# Sheet1.net
KiCad netlist of a schematic drawn in Altium Designer
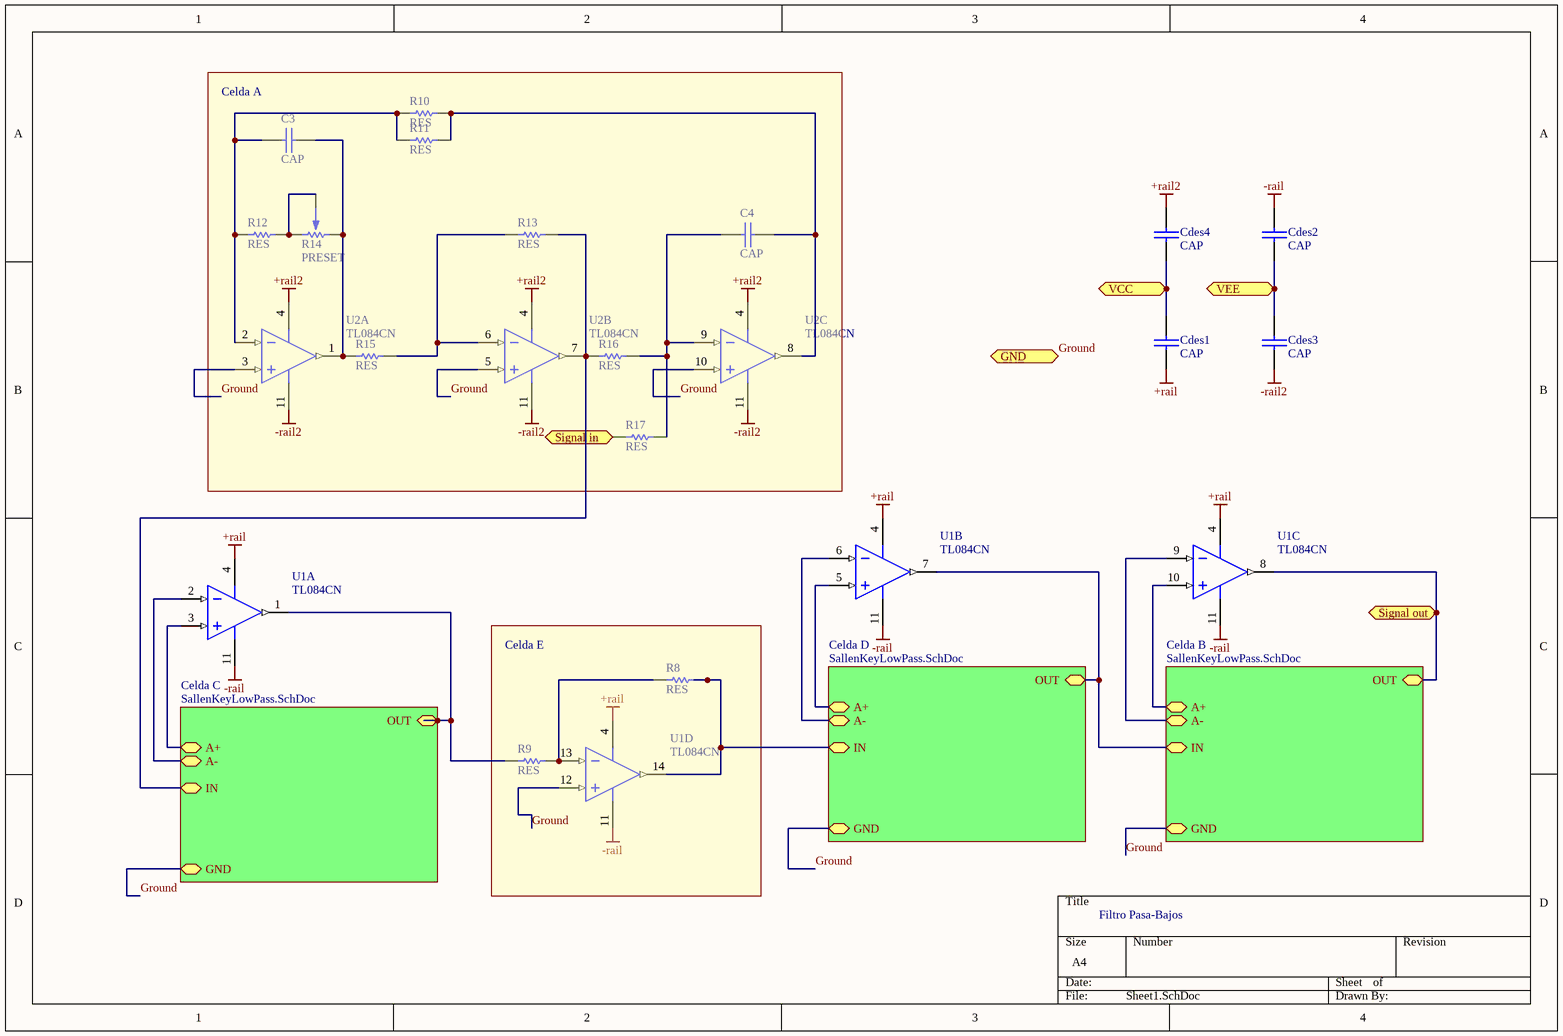
[diagram p0: Sheet1.SchDoc]

(export (version "E")
  (design (tool "Eeschema 10.0.6"))
  (components
    (comp (ref "C3") (value "CAP") (footprint "CAP100") (libsource (lib "LIBEBAL") (part "CAP")))
    (comp (ref "C4") (value "CAP") (footprint "CAP100") (libsource (lib "LIBEBAL") (part "CAP")))
    (comp (ref "Cdes1") (value "CAP") (footprint "CAP100") (libsource (lib "LIBEBAL") (part "CAP")))
    (comp (ref "Cdes2") (value "CAP") (footprint "CAP100") (libsource (lib "LIBEBAL") (part "CAP")))
    (comp (ref "Cdes3") (value "CAP") (footprint "CAP100") (libsource (lib "LIBEBAL") (part "CAP")))
    (comp (ref "Cdes4") (value "CAP") (footprint "CAP100") (libsource (lib "LIBEBAL") (part "CAP")))
    (comp (ref "R8") (value "RES") (footprint "RES300") (libsource (lib "LIBEBAL") (part "RES")))
    (comp (ref "R9") (value "RES") (footprint "RES300") (libsource (lib "LIBEBAL") (part "RES")))
    (comp (ref "R10") (value "RES") (footprint "RES300") (libsource (lib "LIBEBAL") (part "RES")))
    (comp (ref "R11") (value "RES") (footprint "RES300") (libsource (lib "LIBEBAL") (part "RES")))
    (comp (ref "R12") (value "RES") (footprint "RES300") (libsource (lib "LIBEBAL") (part "RES")))
    (comp (ref "R13") (value "RES") (footprint "RES300") (libsource (lib "LIBEBAL") (part "RES")))
    (comp (ref "R14") (value "PRESET") (footprint "PRESET V") (libsource (lib "LIBEBAL") (part "PRESET")))
    (comp (ref "R15") (value "RES") (footprint "RES300") (libsource (lib "LIBEBAL") (part "RES")))
    (comp (ref "R16") (value "RES") (footprint "RES300") (libsource (lib "LIBEBAL") (part "RES")))
    (comp (ref "R17") (value "RES") (footprint "RES300") (libsource (lib "LIBEBAL") (part "RES")))
    (comp (ref "U1")
      (value "TL084CN")
      (footprint "TI-N14")
      (description "JFET-Input Operational Amplifier, 7 to 36 V, 0 to 70 degC, 14-pin DIP (N14), Pb-Free (RoHS)")
      (fields (field (name "MANUFACTURER") "Texas Instruments"))
      (libsource (lib "TI Amplifiers and Linear Operational Amplifier General Purpose") (part "TL084CN"))
    )
    (comp (ref "U2")
      (value "TL084CN")
      (footprint "TI-N14")
      (description "JFET-Input Operational Amplifier, 7 to 36 V, 0 to 70 degC, 14-pin DIP (N14), Pb-Free (RoHS)")
      (fields (field (name "MANUFACTURER") "Texas Instruments"))
      (libsource (lib "TI Amplifiers and Linear Operational Amplifier General Purpose") (part "TL084CN"))
    )
  )
  (nets
    (net (code "1") (name "+rail") (class "Default")
      (node (ref "Cdes1") (pin "2") (pinfunction "2_2") (pintype "passive"))
      (node (ref "U1") (pin "4") (pinfunction "VCC+_4") (pintype "power_in"))
    )
    (net (code "2") (name "+rail2") (class "Default")
      (node (ref "Cdes4") (pin "1") (pinfunction "1_1") (pintype "passive"))
      (node (ref "U2") (pin "4") (pinfunction "VCC+_4") (pintype "power_in"))
    )
    (net (code "3") (name "-rail") (class "Default")
      (node (ref "Cdes2") (pin "1") (pinfunction "1_1") (pintype "passive"))
      (node (ref "U1") (pin "11") (pinfunction "VCC-_11") (pintype "power_in"))
    )
    (net (code "4") (name "-rail2") (class "Default")
      (node (ref "Cdes3") (pin "2") (pinfunction "2_2") (pintype "passive"))
      (node (ref "U2") (pin "11") (pinfunction "VCC-_11") (pintype "power_in"))
    )
    (net (code "5") (name "/A+") (class "Default")
      (node (ref "U1") (pin "10") (pinfunction "IN3+_10") (pintype "input"))
    )
    (net (code "6") (name "/A+_1") (class "Default")
      (node (ref "U1") (pin "3") (pinfunction "IN1+_3") (pintype "input"))
    )
    (net (code "7") (name "/A+_2") (class "Default")
      (node (ref "U1") (pin "5") (pinfunction "IN2+_5") (pintype "input"))
    )
    (net (code "8") (name "/A-") (class "Default")
      (node (ref "U1") (pin "9") (pinfunction "IN3-_9") (pintype "input"))
    )
    (net (code "9") (name "/A-_1") (class "Default")
      (node (ref "U1") (pin "2") (pinfunction "IN1-_2") (pintype "input"))
    )
    (net (code "10") (name "/A-_2") (class "Default")
      (node (ref "U1") (pin "6") (pinfunction "IN2-_6") (pintype "input"))
    )
    (net (code "11") (name "/Ground") (class "Default")
      (node (ref "U1") (pin "12") (pinfunction "IN4+_12") (pintype "input"))
      (node (ref "U2") (pin "10") (pinfunction "IN3+_10") (pintype "input"))
      (node (ref "U2") (pin "3") (pinfunction "IN1+_3") (pintype "input"))
      (node (ref "U2") (pin "5") (pinfunction "IN2+_5") (pintype "input"))
    )
    (net (code "12") (name "/IN") (class "Default")
      (node (ref "U1") (pin "7") (pinfunction "OUT2_7") (pintype "output"))
    )
    (net (code "13") (name "/IN_1") (class "Default")
      (node (ref "R8") (pin "2") (pinfunction "2_2") (pintype "passive"))
      (node (ref "U1") (pin "14") (pinfunction "OUT4_14") (pintype "output"))
    )
    (net (code "14") (name "/IN_2") (class "Default")
      (node (ref "R13") (pin "2") (pinfunction "2_2") (pintype "passive"))
      (node (ref "R16") (pin "1") (pinfunction "1_1") (pintype "passive"))
      (node (ref "U2") (pin "7") (pinfunction "OUT2_7") (pintype "output"))
    )
    (net (code "15") (name "/OUT") (class "Default")
      (node (ref "R9") (pin "1") (pinfunction "1_1") (pintype "passive"))
      (node (ref "U1") (pin "1") (pinfunction "OUT1_1") (pintype "output"))
    )
    (net (code "16") (name "/Signal in") (class "Default")
      (node (ref "R17") (pin "1") (pinfunction "1_1") (pintype "passive"))
    )
    (net (code "17") (name "/Signal out") (class "Default")
      (node (ref "U1") (pin "8") (pinfunction "OUT3_8") (pintype "output"))
    )
    (net (code "18") (name "/VCC") (class "Default")
      (node (ref "Cdes1") (pin "1") (pinfunction "1_1") (pintype "passive"))
      (node (ref "Cdes4") (pin "2") (pinfunction "2_2") (pintype "passive"))
    )
    (net (code "19") (name "/VEE") (class "Default")
      (node (ref "Cdes2") (pin "2") (pinfunction "2_2") (pintype "passive"))
      (node (ref "Cdes3") (pin "1") (pinfunction "1_1") (pintype "passive"))
    )
    (net (code "20") (name "Net-(R12-Pad2)") (class "Default")
      (node (ref "R12") (pin "2") (pinfunction "2_2") (pintype "passive"))
      (node (ref "R14") (pin "1") (pinfunction "1_1") (pintype "passive"))
      (node (ref "R14") (pin "2") (pinfunction "2_2") (pintype "passive"))
    )
    (net (code "21") (name "Net-(U1D-IN4-)") (class "Default")
      (node (ref "R8") (pin "1") (pinfunction "1_1") (pintype "passive"))
      (node (ref "R9") (pin "2") (pinfunction "2_2") (pintype "passive"))
      (node (ref "U1") (pin "13") (pinfunction "IN4-_13") (pintype "input"))
    )
    (net (code "22") (name "Net-(U2A-IN1-)") (class "Default")
      (node (ref "C3") (pin "1") (pinfunction "1_1") (pintype "passive"))
      (node (ref "R10") (pin "1") (pinfunction "1_1") (pintype "passive"))
      (node (ref "R11") (pin "1") (pinfunction "1_1") (pintype "passive"))
      (node (ref "R12") (pin "1") (pinfunction "1_1") (pintype "passive"))
      (node (ref "U2") (pin "2") (pinfunction "IN1-_2") (pintype "input"))
    )
    (net (code "23") (name "Net-(U2A-OUT1)") (class "Default")
      (node (ref "C3") (pin "2") (pinfunction "2_2") (pintype "passive"))
      (node (ref "R14") (pin "3") (pinfunction "3_3") (pintype "passive"))
      (node (ref "R15") (pin "1") (pinfunction "1_1") (pintype "passive"))
      (node (ref "U2") (pin "1") (pinfunction "OUT1_1") (pintype "output"))
    )
    (net (code "24") (name "Net-(U2B-IN2-)") (class "Default")
      (node (ref "R13") (pin "1") (pinfunction "1_1") (pintype "passive"))
      (node (ref "R15") (pin "2") (pinfunction "2_2") (pintype "passive"))
      (node (ref "U2") (pin "6") (pinfunction "IN2-_6") (pintype "input"))
    )
    (net (code "25") (name "Net-(U2C-IN3-)") (class "Default")
      (node (ref "C4") (pin "1") (pinfunction "1_1") (pintype "passive"))
      (node (ref "R16") (pin "2") (pinfunction "2_2") (pintype "passive"))
      (node (ref "R17") (pin "2") (pinfunction "2_2") (pintype "passive"))
      (node (ref "U2") (pin "9") (pinfunction "IN3-_9") (pintype "input"))
    )
    (net (code "26") (name "Net-(U2C-OUT3)") (class "Default")
      (node (ref "C4") (pin "2") (pinfunction "2_2") (pintype "passive"))
      (node (ref "R10") (pin "2") (pinfunction "2_2") (pintype "passive"))
      (node (ref "R11") (pin "2") (pinfunction "2_2") (pintype "passive"))
      (node (ref "U2") (pin "8") (pinfunction "OUT3_8") (pintype "output"))
    )
  )
)
